# STM32F413CG_WM8731.net
KiCad netlist of a schematic drawn in EAGLE
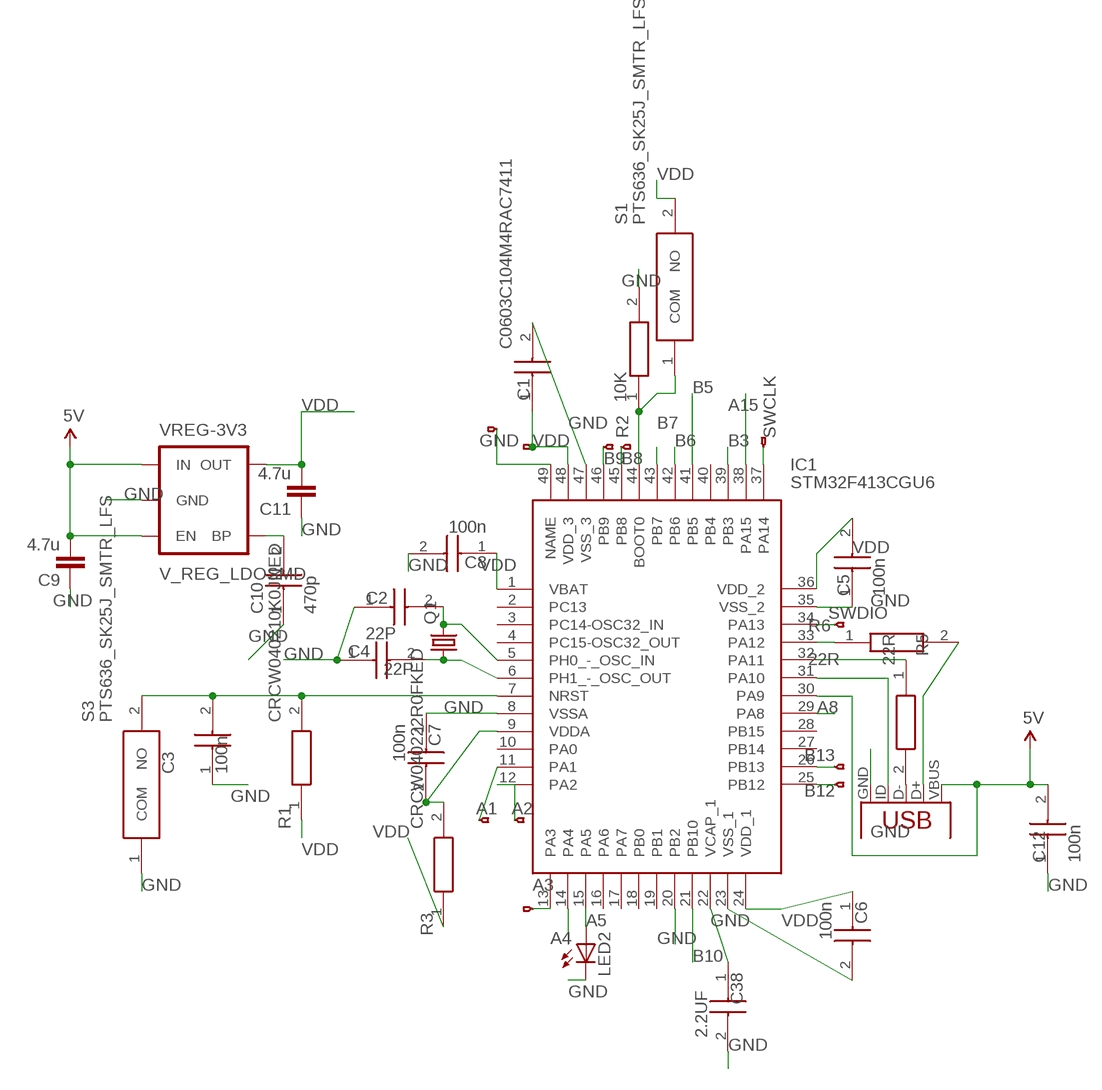
[diagram p0: schematic, sheet 1]
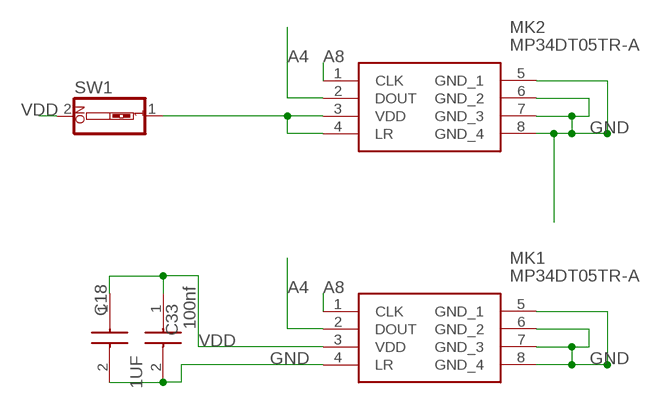
[diagram p1: schematic, sheet 2]
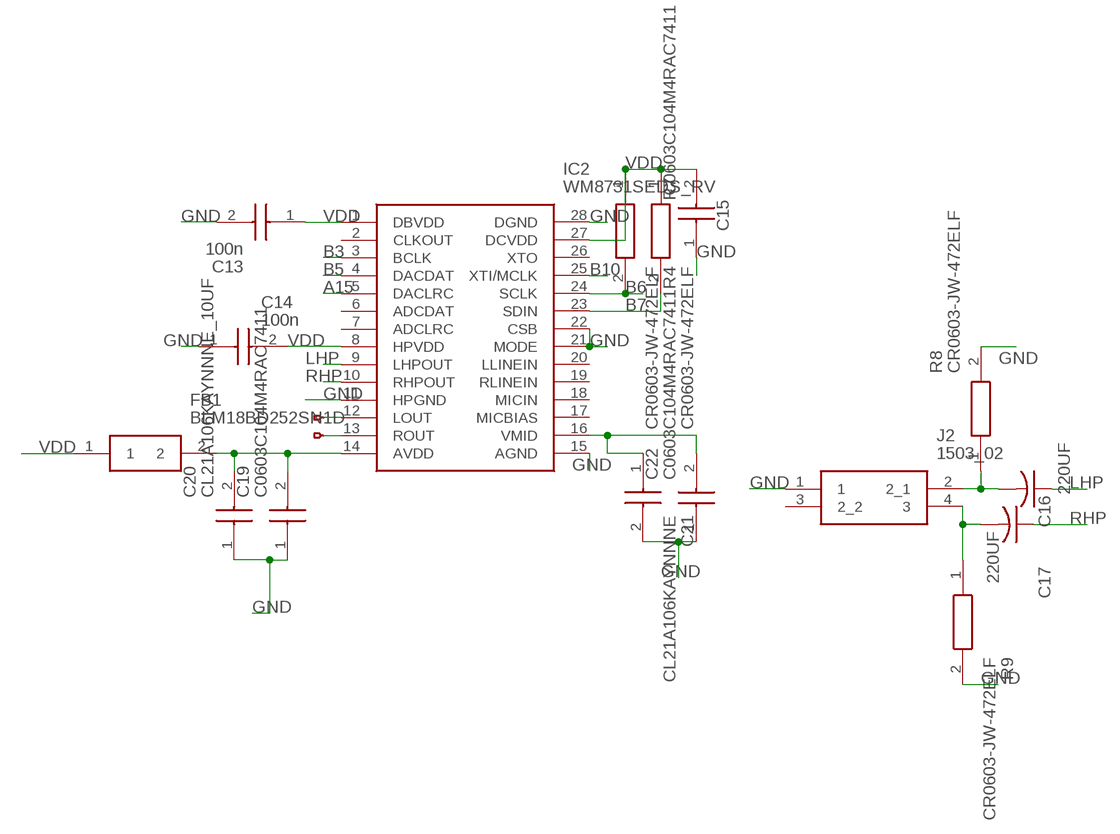
[diagram p2: schematic, sheet 3]

(export (version "E")
  (design (tool "Eeschema 10.0.6"))
  (components
    (comp (ref "C13")
      (value "100n")
      (footprint "eagle-import:CAPC1608X95N")
      (fields
        (field (name "MANUFACTURER_PART_NUMBER") "C0603C104M4RAC7411")
        (field (name "MOUSER_PART_NUMBER") "80-C0603C104M4R7411")
      )
      (libsource (lib "eagle-import") (part "C0603C104M4RAC7411"))
    )
    (comp (ref "C14")
      (value "100n")
      (footprint "eagle-import:CAPC1608X95N")
      (fields
        (field (name "MANUFACTURER_PART_NUMBER") "C0603C104M4RAC7411")
        (field (name "MOUSER_PART_NUMBER") "80-C0603C104M4R7411")
      )
      (libsource (lib "eagle-import") (part "C0603C104M4RAC7411"))
    )
    (comp (ref "C15")
      (value "C0603C104M4RAC7411")
      (footprint "eagle-import:CAPC1608X95N")
      (fields (field (name "MOUSER_PART_NUMBER") "80-C0603C104M4R7411"))
      (libsource (lib "eagle-import") (part "C0603C104M4RAC7411"))
    )
    (comp (ref "C16")
      (value "220UF")
      (footprint "eagle-import:C025-024X044")
      (libsource (lib "eagle-import") (part "C-US025-024X044"))
    )
    (comp (ref "C17")
      (value "220UF")
      (footprint "eagle-import:C025-024X044")
      (libsource (lib "eagle-import") (part "C-US025-024X044"))
    )
    (comp (ref "C19")
      (value "C0603C104M4RAC7411")
      (footprint "eagle-import:CAPC1608X95N")
      (fields (field (name "MOUSER_PART_NUMBER") "80-C0603C104M4R7411"))
      (libsource (lib "eagle-import") (part "C0603C104M4RAC7411_100nF_C0603C104M4RAC7411"))
    )
    (comp (ref "C20")
      (value "CL21A106KAYNNNE_10UF")
      (footprint "eagle-import:CAPC2012X145N")
      (fields (field (name "MANUFACTURER_PART_NUMBER") "CL21A106KAYNNNE"))
      (libsource (lib "eagle-import") (part "CL21A106KAYNNNE"))
    )
    (comp (ref "C21")
      (value "CL21A106KAYNNNE")
      (footprint "eagle-import:CAPC2012X145N")
      (libsource (lib "eagle-import") (part "CL21A106KAYNNNE"))
    )
    (comp (ref "C22")
      (value "C0603C104M4RAC7411")
      (footprint "eagle-import:CAPC1608X95N")
      (fields (field (name "MOUSER_PART_NUMBER") "80-C0603C104M4R7411"))
      (libsource (lib "eagle-import") (part "C0603C104M4RAC7411_100nF_C0603C104M4RAC7411"))
    )
    (comp (ref "FB1")
      (value "BLM18BD252SN1D")
      (footprint "eagle-import:BEADC1608X95N")
      (fields
        (field (name "MOUSER_PART_NUMBER") "81-BLM18BD252SN1D")
        (field (name "RS_PART_NUMBER") "7241321P")
      )
      (libsource (lib "eagle-import") (part "BLM18BD252SN1D"))
    )
    (comp (ref "IC2")
      (value "WM8731SEDS_RV")
      (footprint "eagle-import:SOP65P780X200-28N")
      (fields (field (name "MANUFACTURER_PART_NUMBER") "WM8731SEDS/RV"))
      (libsource (lib "eagle-import") (part "WM8731SEDS_RV"))
    )
    (comp (ref "J2")
      (value "1503_02")
      (footprint "eagle-import:150302")
      (fields (field (name "MANUFACTURER_PART_NUMBER") "1503 02"))
      (libsource (lib "eagle-import") (part "1503_02"))
    )
    (comp (ref "JP12")
      (value "HEADERHOLE-HEADERHOLE")
      (footprint "eagle-import:1X1-HEADER-HOLE")
      (libsource (lib "eagle-import") (part "HEADERHOLE-HEADERHOLE"))
    )
    (comp (ref "JP13")
      (value "HEADERHOLE-HEADERHOLE")
      (footprint "eagle-import:1X1-HEADER-HOLE")
      (libsource (lib "eagle-import") (part "HEADERHOLE-HEADERHOLE"))
    )
    (comp (ref "R4")
      (value "CR0603-JW-472ELF")
      (footprint "eagle-import:RESC1608X55N")
      (fields
        (field (name "MOUSER_PART_NUMBER") "652-CR0603-JW-472ELF")
        (field (name "RS_PART_NUMBER") "7408956P")
      )
      (libsource (lib "eagle-import") (part "CR0603-JW-472ELF"))
    )
    (comp (ref "R7")
      (value "CR0603-JW-472ELF")
      (footprint "eagle-import:RESC1608X55N")
      (fields
        (field (name "MOUSER_PART_NUMBER") "652-CR0603-JW-472ELF")
        (field (name "RS_PART_NUMBER") "7408956P")
      )
      (libsource (lib "eagle-import") (part "CR0603-JW-472ELF"))
    )
    (comp (ref "R8")
      (value "CR0603-JW-472ELF")
      (footprint "eagle-import:RESC1608X55N")
      (fields
        (field (name "MOUSER_PART_NUMBER") "652-CR0603-JW-472ELF")
        (field (name "RS_PART_NUMBER") "7408956P")
      )
      (libsource (lib "eagle-import") (part "CR0603-JW-472ELF"))
    )
    (comp (ref "R9")
      (value "CR0603-JW-472ELF")
      (footprint "eagle-import:RESC1608X55N")
      (fields
        (field (name "MOUSER_PART_NUMBER") "652-CR0603-JW-472ELF")
        (field (name "RS_PART_NUMBER") "7408956P")
      )
      (libsource (lib "eagle-import") (part "CR0603-JW-472ELF"))
    )
    (comp (ref "C18")
      (value "1UF")
      (footprint "eagle-import:CAPC1005X55N")
      (fields
        (field (name "MANUFACTURER_PART_NUMBER") "CC0402KRX5R6BB105")
        (field (name "MOUSER_PART_NUMBER") "603-CC402KRX5R6BB105")
      )
      (libsource (lib "eagle-import") (part "CC0402KRX5R6BB105"))
    )
    (comp (ref "C33")
      (value "100nf")
      (footprint "eagle-import:CAPC1608X95N")
      (fields
        (field (name "MANUFACTURER_PART_NUMBER") "C0603C104M4RAC7411")
        (field (name "MOUSER_PART_NUMBER") "80-C0603C104M4R7411")
      )
      (libsource (lib "eagle-import") (part "C0603C104M4RAC7411"))
    )
    (comp (ref "MK1")
      (value "MP34DT05TR-A")
      (footprint "eagle-import:MP34DT05TRA")
      (fields (field (name "MOUSER_PART_NUMBER") "511-MP34DT05TR-A"))
      (libsource (lib "eagle-import") (part "MP34DT05TR-A"))
    )
    (comp (ref "MK2")
      (value "MP34DT05TR-A")
      (footprint "eagle-import:MP34DT05TRA")
      (fields (field (name "MOUSER_PART_NUMBER") "511-MP34DT05TR-A"))
      (libsource (lib "eagle-import") (part "MP34DT05TR-A"))
    )
    (comp (ref "SW1")
      (value "SW_DIP-1")
      (footprint "eagle-import:EDG-01")
      (libsource (lib "eagle-import") (part "SW_DIP-1"))
    )
    (comp (ref "C1")
      (value "C0603C104M4RAC7411")
      (footprint "eagle-import:CAPC1608X95N")
      (fields (field (name "MOUSER_PART_NUMBER") "80-C0603C104M4R7411"))
      (libsource (lib "eagle-import") (part "C0603C104M4RAC7411"))
    )
    (comp (ref "C2")
      (value "22P")
      (footprint "eagle-import:CAPC1608X80N")
      (fields
        (field (name "MANUFACTURER_PART_NUMBER") "C1608C0G1H150J080AA")
        (field (name "MOUSER_PART_NUMBER") "810-C1608C0G1H150J")
        (field (name "RS_PART_NUMBER") "7882935")
      )
      (libsource (lib "eagle-import") (part "C1608C0G1H150J080AA"))
    )
    (comp (ref "C3")
      (value "100n")
      (footprint "eagle-import:CAPC1608X95N")
      (fields
        (field (name "MANUFACTURER_PART_NUMBER") "C0603C104M4RAC7411")
        (field (name "MOUSER_PART_NUMBER") "80-C0603C104M4R7411")
      )
      (libsource (lib "eagle-import") (part "C0603C104M4RAC7411"))
    )
    (comp (ref "C4")
      (value "22P")
      (footprint "eagle-import:CAPC1608X80N")
      (fields
        (field (name "MANUFACTURER_PART_NUMBER") "C1608C0G1H150J080AA")
        (field (name "MOUSER_PART_NUMBER") "810-C1608C0G1H150J")
        (field (name "RS_PART_NUMBER") "7882935")
      )
      (libsource (lib "eagle-import") (part "C1608C0G1H150J080AA"))
    )
    (comp (ref "C5")
      (value "100n")
      (footprint "eagle-import:CAPC1608X95N")
      (fields
        (field (name "MANUFACTURER_PART_NUMBER") "C0603C104M4RAC7411")
        (field (name "MOUSER_PART_NUMBER") "80-C0603C104M4R7411")
      )
      (libsource (lib "eagle-import") (part "C0603C104M4RAC7411"))
    )
    (comp (ref "C6")
      (value "100n")
      (footprint "eagle-import:CAPC1608X95N")
      (fields
        (field (name "MANUFACTURER_PART_NUMBER") "C0603C104M4RAC7411")
        (field (name "MOUSER_PART_NUMBER") "80-C0603C104M4R7411")
      )
      (libsource (lib "eagle-import") (part "C0603C104M4RAC7411"))
    )
    (comp (ref "C7")
      (value "100n")
      (footprint "eagle-import:CAPC1608X95N")
      (fields
        (field (name "MANUFACTURER_PART_NUMBER") "C0603C104M4RAC7411")
        (field (name "MOUSER_PART_NUMBER") "80-C0603C104M4R7411")
      )
      (libsource (lib "eagle-import") (part "C0603C104M4RAC7411"))
    )
    (comp (ref "C8")
      (value "100n")
      (footprint "eagle-import:CAPC1608X95N")
      (fields
        (field (name "MANUFACTURER_PART_NUMBER") "C0603C104M4RAC7411")
        (field (name "MOUSER_PART_NUMBER") "80-C0603C104M4R7411")
      )
      (libsource (lib "eagle-import") (part "C0603C104M4RAC7411"))
    )
    (comp (ref "C9")
      (value "4.7u")
      (footprint "eagle-import:C2.5-3")
      (libsource (lib "eagle-import") (part "C2,5-3"))
    )
    (comp (ref "C10")
      (value "470p")
      (footprint "eagle-import:CAPC1608X87N")
      (fields
        (field (name "MANUFACTURER_PART_NUMBER") "C0603C471K3RACTU")
        (field (name "MOUSER_PART_NUMBER") "80-C0603C471K3R")
      )
      (libsource (lib "eagle-import") (part "C0603C471K3RACTU"))
    )
    (comp (ref "C11")
      (value "4.7u")
      (footprint "eagle-import:C2.5-3")
      (libsource (lib "eagle-import") (part "C2,5-3"))
    )
    (comp (ref "C12")
      (value "100n")
      (footprint "eagle-import:CAPC1608X95N")
      (fields
        (field (name "MANUFACTURER_PART_NUMBER") "C0603C104M4RAC7411")
        (field (name "MOUSER_PART_NUMBER") "80-C0603C104M4R7411")
      )
      (libsource (lib "eagle-import") (part "C0603C104M4RAC7411"))
    )
    (comp (ref "C38")
      (value "2.2UF")
      (footprint "eagle-import:CAPC2012X145N")
      (fields
        (field (name "MANUFACTURER_PART_NUMBER") "C2012X7R1E225K125AB")
        (field (name "MOUSER_PART_NUMBER") "810-C2012X7R1E225K")
        (field (name "RS_PART_NUMBER") "9159394P")
      )
      (libsource (lib "eagle-import") (part "C2012X7R1E225K125AB"))
    )
    (comp (ref "IC1")
      (value "STM32F413CGU6")
      (footprint "eagle-import:QFN50P700X700X60-49N")
      (fields (field (name "MOUSER_PART_NUMBER") "511-STM32F413CGU6"))
      (libsource (lib "eagle-import") (part "STM32F413CGU6"))
    )
    (comp (ref "JP1")
      (value "HEADERHOLE-HEADERHOLE")
      (footprint "eagle-import:1X1-HEADER-HOLE")
      (libsource (lib "eagle-import") (part "HEADERHOLE-HEADERHOLE"))
    )
    (comp (ref "JP2")
      (value "HEADERHOLE-HEADERHOLE")
      (footprint "eagle-import:1X1-HEADER-HOLE")
      (libsource (lib "eagle-import") (part "HEADERHOLE-HEADERHOLE"))
    )
    (comp (ref "JP3")
      (value "HEADERHOLE-HEADERHOLE")
      (footprint "eagle-import:1X1-HEADER-HOLE")
      (libsource (lib "eagle-import") (part "HEADERHOLE-HEADERHOLE"))
    )
    (comp (ref "JP4")
      (value "HEADERHOLE-HEADERHOLE")
      (footprint "eagle-import:1X1-HEADER-HOLE")
      (libsource (lib "eagle-import") (part "HEADERHOLE-HEADERHOLE"))
    )
    (comp (ref "JP5")
      (value "HEADERHOLE-HEADERHOLE")
      (footprint "eagle-import:1X1-HEADER-HOLE")
      (libsource (lib "eagle-import") (part "HEADERHOLE-HEADERHOLE"))
    )
    (comp (ref "JP6")
      (value "HEADERHOLE-HEADERHOLE")
      (footprint "eagle-import:1X1-HEADER-HOLE")
      (libsource (lib "eagle-import") (part "HEADERHOLE-HEADERHOLE"))
    )
    (comp (ref "JP7")
      (value "HEADERHOLE-HEADERHOLE")
      (footprint "eagle-import:1X1-HEADER-HOLE")
      (libsource (lib "eagle-import") (part "HEADERHOLE-HEADERHOLE"))
    )
    (comp (ref "JP8")
      (value "HEADERHOLE-HEADERHOLE")
      (footprint "eagle-import:1X1-HEADER-HOLE")
      (libsource (lib "eagle-import") (part "HEADERHOLE-HEADERHOLE"))
    )
    (comp (ref "JP9")
      (value "HEADERHOLE-HEADERHOLE")
      (footprint "eagle-import:1X1-HEADER-HOLE")
      (libsource (lib "eagle-import") (part "HEADERHOLE-HEADERHOLE"))
    )
    (comp (ref "JP10")
      (value "HEADERHOLE-HEADERHOLE")
      (footprint "eagle-import:1X1-HEADER-HOLE")
      (libsource (lib "eagle-import") (part "HEADERHOLE-HEADERHOLE"))
    )
    (comp (ref "JP11")
      (value "HEADERHOLE-HEADERHOLE")
      (footprint "eagle-import:1X1-HEADER-HOLE")
      (libsource (lib "eagle-import") (part "HEADERHOLE-HEADERHOLE"))
    )
    (comp (ref "LED2")
      (value "LED0603")
      (footprint "eagle-import:LED-0603")
      (libsource (lib "eagle-import") (part "LED0603"))
    )
    (comp (ref "Q1")
      (value "CRYSTALHC49S")
      (footprint "eagle-import:HC49_S")
      (libsource (lib "eagle-import") (part "CRYSTALHC49S"))
    )
    (comp (ref "R1")
      (value "CRCW040210K0JNED")
      (footprint "eagle-import:RESC1005X40N")
      (fields (field (name "MOUSER_PART_NUMBER") "71-CRCW0402J-10K-E3"))
      (libsource (lib "eagle-import") (part "CRCW040210K0JNED"))
    )
    (comp (ref "R2")
      (value "10K")
      (footprint "eagle-import:RESC1005X40N")
      (fields
        (field (name "MANUFACTURER_PART_NUMBER") "CRCW040210K0JNED")
        (field (name "MOUSER_PART_NUMBER") "71-CRCW0402J-10K-E3")
      )
      (libsource (lib "eagle-import") (part "CRCW040210K0JNED"))
    )
    (comp (ref "R3")
      (value "CRCW040222R0FKED")
      (footprint "eagle-import:RESC1005X40N")
      (fields
        (field (name "MOUSER_PART_NUMBER") "71-CRCW0402-22-E3")
        (field (name "RS_PART_NUMBER") "6788983P")
      )
      (libsource (lib "eagle-import") (part "CRCW040222R0FKED"))
    )
    (comp (ref "R5")
      (value "22R")
      (footprint "eagle-import:RESC1005X40N")
      (fields
        (field (name "MANUFACTURER_PART_NUMBER") "CRCW040222R0FKED")
        (field (name "MOUSER_PART_NUMBER") "71-CRCW0402-22-E3")
        (field (name "RS_PART_NUMBER") "6788983P")
      )
      (libsource (lib "eagle-import") (part "CRCW040222R0FKED"))
    )
    (comp (ref "R6")
      (value "22R")
      (footprint "eagle-import:RESC1005X40N")
      (fields
        (field (name "MANUFACTURER_PART_NUMBER") "CRCW040222R0FKED")
        (field (name "MOUSER_PART_NUMBER") "71-CRCW0402-22-E3")
        (field (name "RS_PART_NUMBER") "6788983P")
      )
      (libsource (lib "eagle-import") (part "CRCW040222R0FKED"))
    )
    (comp (ref "S1")
      (value "PTS636_SK25J_SMTR_LFS")
      (footprint "eagle-import:PTS636SK25JSMTRLFS")
      (fields
        (field (name "MANUFACTURER_PART_NUMBER") "PTS636 SK25J SMTR LFS")
        (field (name "MOUSER_PART_NUMBER") "611-PTS636SK25JSMTRL")
      )
      (libsource (lib "eagle-import") (part "PTS636_SK25J_SMTR_LFS"))
    )
    (comp (ref "S3")
      (value "PTS636_SK25J_SMTR_LFS")
      (footprint "eagle-import:PTS636SK25JSMTRLFS")
      (fields
        (field (name "MANUFACTURER_PART_NUMBER") "PTS636 SK25J SMTR LFS")
        (field (name "MOUSER_PART_NUMBER") "611-PTS636SK25JSMTRL")
      )
      (libsource (lib "eagle-import") (part "PTS636_SK25J_SMTR_LFS"))
    )
    (comp (ref "VREG-3V3")
      (value "V_REG_LDOSMD")
      (footprint "eagle-import:SOT23-5")
      (libsource (lib "eagle-import") (part "V_REG_LDOSMD"))
    )
    (comp (ref "X1")
      (value "USB-MICROB-SMD")
      (footprint "eagle-import:USB-MICROB-SMD")
      (libsource (lib "eagle-import") (part "USB-MICROB-SMD"))
    )
  )
  (nets
    (net (code "1") (name "5V") (class "Default")
      (node (ref "C12") (pin "2") (pinfunction "2_2") (pintype "bidirectional"))
      (node (ref "C9") (pin "2") (pinfunction "2_2") (pintype "passive"))
      (node (ref "IC1") (pin "30") (pinfunction "PA9_30") (pintype "bidirectional"))
      (node (ref "VREG-3V3") (pin "1") (pinfunction "IN_1") (pintype "input"))
      (node (ref "VREG-3V3") (pin "3") (pinfunction "EN_3") (pintype "input"))
      (node (ref "X1") (pin "VBUS") (pinfunction "VBUS_VBUS") (pintype "bidirectional"))
    )
    (net (code "2") (name "A1") (class "Default")
      (node (ref "IC1") (pin "11") (pinfunction "PA1_11") (pintype "bidirectional"))
      (node (ref "JP8") (pin "1") (pinfunction "P$1_1") (pintype "bidirectional"))
    )
    (net (code "3") (name "A2") (class "Default")
      (node (ref "IC1") (pin "12") (pinfunction "PA2_12") (pintype "bidirectional"))
      (node (ref "JP9") (pin "1") (pinfunction "P$1_1") (pintype "bidirectional"))
    )
    (net (code "4") (name "A3") (class "Default")
      (node (ref "IC1") (pin "13") (pinfunction "PA3_13") (pintype "bidirectional"))
      (node (ref "JP10") (pin "1") (pinfunction "P$1_1") (pintype "bidirectional"))
    )
    (net (code "5") (name "A4") (class "Default")
      (node (ref "IC1") (pin "14") (pinfunction "PA4_14") (pintype "bidirectional"))
      (node (ref "MK1") (pin "2") (pinfunction "DOUT_2") (pintype "bidirectional"))
      (node (ref "MK2") (pin "2") (pinfunction "DOUT_2") (pintype "bidirectional"))
    )
    (net (code "6") (name "A5") (class "Default")
      (node (ref "IC1") (pin "15") (pinfunction "PA5_15") (pintype "bidirectional"))
      (node (ref "LED2") (pin "A") (pinfunction "A_A") (pintype "passive"))
    )
    (net (code "7") (name "A8") (class "Default")
      (node (ref "IC1") (pin "29") (pinfunction "PA8_29") (pintype "bidirectional"))
      (node (ref "MK1") (pin "1") (pinfunction "CLK_1") (pintype "bidirectional"))
      (node (ref "MK2") (pin "1") (pinfunction "CLK_1") (pintype "bidirectional"))
    )
    (net (code "8") (name "A15") (class "Default")
      (node (ref "IC1") (pin "38") (pinfunction "PA15_38") (pintype "bidirectional"))
      (node (ref "IC2") (pin "5") (pinfunction "DACLRC_5") (pintype "bidirectional"))
    )
    (net (code "9") (name "B3") (class "Default")
      (node (ref "IC1") (pin "39") (pinfunction "PB3_39") (pintype "bidirectional"))
      (node (ref "IC2") (pin "3") (pinfunction "BCLK_3") (pintype "bidirectional"))
    )
    (net (code "10") (name "B5") (class "Default")
      (node (ref "IC1") (pin "41") (pinfunction "PB5_41") (pintype "bidirectional"))
      (node (ref "IC2") (pin "4") (pinfunction "DACDAT_4") (pintype "bidirectional"))
    )
    (net (code "11") (name "B6") (class "Default")
      (node (ref "IC1") (pin "42") (pinfunction "PB6_42") (pintype "bidirectional"))
      (node (ref "IC2") (pin "24") (pinfunction "SCLK_24") (pintype "bidirectional"))
      (node (ref "R4") (pin "2") (pinfunction "2_2") (pintype "bidirectional"))
    )
    (net (code "12") (name "B7") (class "Default")
      (node (ref "IC1") (pin "43") (pinfunction "PB7_43") (pintype "bidirectional"))
      (node (ref "IC2") (pin "23") (pinfunction "SDIN_23") (pintype "bidirectional"))
      (node (ref "R7") (pin "2") (pinfunction "2_2") (pintype "bidirectional"))
    )
    (net (code "13") (name "B8") (class "Default")
      (node (ref "IC1") (pin "45") (pinfunction "PB8_45") (pintype "bidirectional"))
      (node (ref "JP5") (pin "1") (pinfunction "P$1_1") (pintype "bidirectional"))
    )
    (net (code "14") (name "B9") (class "Default")
      (node (ref "IC1") (pin "46") (pinfunction "PB9_46") (pintype "bidirectional"))
      (node (ref "JP11") (pin "1") (pinfunction "P$1_1") (pintype "bidirectional"))
    )
    (net (code "15") (name "B10") (class "Default")
      (node (ref "IC1") (pin "21") (pinfunction "PB10_21") (pintype "bidirectional"))
      (node (ref "IC2") (pin "25") (pinfunction "XTI/MCLK_25") (pintype "bidirectional"))
    )
    (net (code "16") (name "B12") (class "Default")
      (node (ref "IC1") (pin "25") (pinfunction "PB12_25") (pintype "bidirectional"))
      (node (ref "JP7") (pin "1") (pinfunction "P$1_1") (pintype "bidirectional"))
    )
    (net (code "17") (name "B13") (class "Default")
      (node (ref "IC1") (pin "26") (pinfunction "PB13_26") (pintype "bidirectional"))
      (node (ref "JP6") (pin "1") (pinfunction "P$1_1") (pintype "bidirectional"))
    )
    (net (code "18") (name "GND") (class "Default")
      (node (ref "C1") (pin "2") (pinfunction "2_2") (pintype "bidirectional"))
      (node (ref "C10") (pin "1") (pinfunction "1_1") (pintype "bidirectional"))
      (node (ref "C11") (pin "1") (pinfunction "1_1") (pintype "passive"))
      (node (ref "C12") (pin "1") (pinfunction "1_1") (pintype "bidirectional"))
      (node (ref "C13") (pin "2") (pinfunction "2_2") (pintype "bidirectional"))
      (node (ref "C14") (pin "1") (pinfunction "1_1") (pintype "bidirectional"))
      (node (ref "C15") (pin "1") (pinfunction "1_1") (pintype "bidirectional"))
      (node (ref "C18") (pin "2") (pinfunction "C2_2") (pintype "bidirectional"))
      (node (ref "C19") (pin "1") (pinfunction "1_1") (pintype "bidirectional"))
      (node (ref "C2") (pin "1") (pinfunction "1_1") (pintype "bidirectional"))
      (node (ref "C20") (pin "1") (pinfunction "1_1") (pintype "bidirectional"))
      (node (ref "C21") (pin "2") (pinfunction "2_2") (pintype "bidirectional"))
      (node (ref "C22") (pin "1") (pinfunction "1_1") (pintype "bidirectional"))
      (node (ref "C3") (pin "1") (pinfunction "1_1") (pintype "bidirectional"))
      (node (ref "C33") (pin "2") (pinfunction "2_2") (pintype "bidirectional"))
      (node (ref "C38") (pin "2") (pinfunction "2_2") (pintype "bidirectional"))
      (node (ref "C4") (pin "1") (pinfunction "1_1") (pintype "bidirectional"))
      (node (ref "C5") (pin "1") (pinfunction "1_1") (pintype "bidirectional"))
      (node (ref "C6") (pin "2") (pinfunction "2_2") (pintype "bidirectional"))
      (node (ref "C7") (pin "1") (pinfunction "1_1") (pintype "bidirectional"))
      (node (ref "C8") (pin "2") (pinfunction "2_2") (pintype "bidirectional"))
      (node (ref "C9") (pin "1") (pinfunction "1_1") (pintype "passive"))
      (node (ref "IC1") (pin "20") (pinfunction "PB2_20") (pintype "bidirectional"))
      (node (ref "IC1") (pin "23") (pinfunction "VSS_1_23") (pintype "power_in"))
      (node (ref "IC1") (pin "35") (pinfunction "VSS_2_35") (pintype "power_in"))
      (node (ref "IC1") (pin "47") (pinfunction "VSS_3_47") (pintype "power_in"))
      (node (ref "IC1") (pin "49") (pinfunction "NAME_49") (pintype "bidirectional"))
      (node (ref "IC1") (pin "8") (pinfunction "VSSA_8") (pintype "power_in"))
      (node (ref "IC2") (pin "11") (pinfunction "HPGND_11") (pintype "bidirectional"))
      (node (ref "IC2") (pin "15") (pinfunction "AGND_15") (pintype "bidirectional"))
      (node (ref "IC2") (pin "21") (pinfunction "MODE_21") (pintype "bidirectional"))
      (node (ref "IC2") (pin "22") (pinfunction "CSB_22") (pintype "bidirectional"))
      (node (ref "IC2") (pin "28") (pinfunction "DGND_28") (pintype "bidirectional"))
      (node (ref "J2") (pin "1") (pinfunction "1_1") (pintype "bidirectional"))
      (node (ref "JP1") (pin "1") (pinfunction "P$1_1") (pintype "bidirectional"))
      (node (ref "LED2") (pin "C") (pinfunction "C_C") (pintype "passive"))
      (node (ref "MK1") (pin "4") (pinfunction "LR_4") (pintype "bidirectional"))
      (node (ref "MK1") (pin "5") (pinfunction "GND_1_5") (pintype "bidirectional"))
      (node (ref "MK1") (pin "6") (pinfunction "GND_2_6") (pintype "bidirectional"))
      (node (ref "MK1") (pin "7") (pinfunction "GND_3_7") (pintype "bidirectional"))
      (node (ref "MK1") (pin "8") (pinfunction "GND_4_8") (pintype "bidirectional"))
      (node (ref "MK2") (pin "5") (pinfunction "GND_1_5") (pintype "bidirectional"))
      (node (ref "MK2") (pin "6") (pinfunction "GND_2_6") (pintype "bidirectional"))
      (node (ref "MK2") (pin "7") (pinfunction "GND_3_7") (pintype "bidirectional"))
      (node (ref "MK2") (pin "8") (pinfunction "GND_4_8") (pintype "bidirectional"))
      (node (ref "R2") (pin "2") (pinfunction "2_2") (pintype "bidirectional"))
      (node (ref "R8") (pin "2") (pinfunction "2_2") (pintype "bidirectional"))
      (node (ref "R9") (pin "2") (pinfunction "2_2") (pintype "bidirectional"))
      (node (ref "S3") (pin "1") (pinfunction "COM_1") (pintype "bidirectional"))
      (node (ref "VREG-3V3") (pin "2") (pinfunction "GND_2") (pintype "input"))
      (node (ref "X1") (pin "GND") (pinfunction "GND_GND") (pintype "bidirectional"))
    )
    (net (code "19") (name "LHP") (class "Default")
      (node (ref "C16") (pin "1") (pinfunction "1_1") (pintype "passive"))
      (node (ref "IC2") (pin "9") (pinfunction "LHPOUT_9") (pintype "bidirectional"))
    )
    (net (code "20") (name "Net-(IC1-BOOT0)") (class "Default")
      (node (ref "IC1") (pin "44") (pinfunction "BOOT0_44") (pintype "bidirectional"))
      (node (ref "R2") (pin "1") (pinfunction "1_1") (pintype "bidirectional"))
      (node (ref "S1") (pin "1") (pinfunction "COM_1") (pintype "bidirectional"))
    )
    (net (code "21") (name "Net-(IC1-NRST)") (class "Default")
      (node (ref "C3") (pin "2") (pinfunction "2_2") (pintype "bidirectional"))
      (node (ref "IC1") (pin "7") (pinfunction "NRST_7") (pintype "bidirectional"))
      (node (ref "R1") (pin "2") (pinfunction "2_2") (pintype "bidirectional"))
      (node (ref "S3") (pin "2") (pinfunction "NO_2") (pintype "bidirectional"))
    )
    (net (code "22") (name "Net-(IC1-PA10)") (class "Default")
      (node (ref "IC1") (pin "31") (pinfunction "PA10_31") (pintype "bidirectional"))
      (node (ref "X1") (pin "ID") (pinfunction "ID_ID") (pintype "bidirectional"))
    )
    (net (code "23") (name "Net-(IC1-PA11)") (class "Default")
      (node (ref "IC1") (pin "32") (pinfunction "PA11_32") (pintype "bidirectional"))
      (node (ref "R5") (pin "1") (pinfunction "1_1") (pintype "bidirectional"))
    )
    (net (code "24") (name "Net-(IC1-PA12)") (class "Default")
      (node (ref "IC1") (pin "33") (pinfunction "PA12_33") (pintype "bidirectional"))
      (node (ref "R6") (pin "1") (pinfunction "1_1") (pintype "bidirectional"))
    )
    (net (code "25") (name "Net-(IC1-PH0_-_OSC_IN)") (class "Default")
      (node (ref "C2") (pin "2") (pinfunction "2_2") (pintype "bidirectional"))
      (node (ref "IC1") (pin "5") (pinfunction "PH0_-_OSC_IN_5") (pintype "bidirectional"))
      (node (ref "Q1") (pin "2") (pinfunction "2_2") (pintype "passive"))
    )
    (net (code "26") (name "Net-(IC1-PH1_-_OSC_OUT)") (class "Default")
      (node (ref "C4") (pin "2") (pinfunction "2_2") (pintype "bidirectional"))
      (node (ref "IC1") (pin "6") (pinfunction "PH1_-_OSC_OUT_6") (pintype "bidirectional"))
      (node (ref "Q1") (pin "1") (pinfunction "1_1") (pintype "passive"))
    )
    (net (code "27") (name "Net-(IC1-VCAP_1)") (class "Default")
      (node (ref "C38") (pin "1") (pinfunction "1_1") (pintype "bidirectional"))
      (node (ref "IC1") (pin "22") (pinfunction "VCAP_1_22") (pintype "power_in"))
    )
    (net (code "28") (name "Net-(IC1-VDDA)") (class "Default")
      (node (ref "C7") (pin "2") (pinfunction "2_2") (pintype "bidirectional"))
      (node (ref "IC1") (pin "9") (pinfunction "VDDA_9") (pintype "power_in"))
      (node (ref "R3") (pin "2") (pinfunction "2_2") (pintype "bidirectional"))
    )
    (net (code "29") (name "Net-(IC2-AVDD)") (class "Default")
      (node (ref "C19") (pin "2") (pinfunction "2_2") (pintype "bidirectional"))
      (node (ref "C20") (pin "2") (pinfunction "2_2") (pintype "bidirectional"))
      (node (ref "FB1") (pin "2") (pinfunction "2_2") (pintype "bidirectional"))
      (node (ref "IC2") (pin "14") (pinfunction "AVDD_14") (pintype "bidirectional"))
    )
    (net (code "30") (name "Net-(IC2-LOUT)") (class "Default")
      (node (ref "IC2") (pin "12") (pinfunction "LOUT_12") (pintype "bidirectional"))
      (node (ref "JP13") (pin "1") (pinfunction "P$1_1") (pintype "bidirectional"))
    )
    (net (code "31") (name "Net-(IC2-ROUT)") (class "Default")
      (node (ref "IC2") (pin "13") (pinfunction "ROUT_13") (pintype "bidirectional"))
      (node (ref "JP12") (pin "1") (pinfunction "P$1_1") (pintype "bidirectional"))
    )
    (net (code "32") (name "Net-(IC2-VMID)") (class "Default")
      (node (ref "C21") (pin "1") (pinfunction "1_1") (pintype "bidirectional"))
      (node (ref "C22") (pin "2") (pinfunction "2_2") (pintype "bidirectional"))
      (node (ref "IC2") (pin "16") (pinfunction "VMID_16") (pintype "bidirectional"))
    )
    (net (code "33") (name "Net-(J2-2_1)") (class "Default")
      (node (ref "C16") (pin "2") (pinfunction "2_2") (pintype "passive"))
      (node (ref "J2") (pin "2") (pinfunction "2_1_2") (pintype "bidirectional"))
      (node (ref "R8") (pin "1") (pinfunction "1_1") (pintype "bidirectional"))
    )
    (net (code "34") (name "Net-(J2-3)") (class "Default")
      (node (ref "C17") (pin "2") (pinfunction "2_2") (pintype "passive"))
      (node (ref "J2") (pin "4") (pinfunction "3_4") (pintype "bidirectional"))
      (node (ref "R9") (pin "1") (pinfunction "1_1") (pintype "bidirectional"))
    )
    (net (code "35") (name "Net-(MK2-LR)") (class "Default")
      (node (ref "MK2") (pin "3") (pinfunction "VDD_3") (pintype "bidirectional"))
      (node (ref "MK2") (pin "4") (pinfunction "LR_4") (pintype "bidirectional"))
      (node (ref "SW1") (pin "1") (pinfunction "1_1") (pintype "passive"))
    )
    (net (code "36") (name "Net-(R5-Pad2)") (class "Default")
      (node (ref "R5") (pin "2") (pinfunction "2_2") (pintype "bidirectional"))
      (node (ref "X1") (pin "D-") (pinfunction "D-_D-") (pintype "bidirectional"))
    )
    (net (code "37") (name "Net-(R6-Pad2)") (class "Default")
      (node (ref "R6") (pin "2") (pinfunction "2_2") (pintype "bidirectional"))
      (node (ref "X1") (pin "D+") (pinfunction "D+_D+") (pintype "bidirectional"))
    )
    (net (code "38") (name "Net-(VREG-3V3-BP)") (class "Default")
      (node (ref "C10") (pin "2") (pinfunction "2_2") (pintype "bidirectional"))
      (node (ref "VREG-3V3") (pin "4") (pinfunction "BP_4") (pintype "input"))
    )
    (net (code "39") (name "RHP") (class "Default")
      (node (ref "C17") (pin "1") (pinfunction "1_1") (pintype "passive"))
      (node (ref "IC2") (pin "10") (pinfunction "RHPOUT_10") (pintype "bidirectional"))
    )
    (net (code "40") (name "SWCLK") (class "Default")
      (node (ref "IC1") (pin "37") (pinfunction "PA14_37") (pintype "bidirectional"))
      (node (ref "JP2") (pin "1") (pinfunction "P$1_1") (pintype "bidirectional"))
    )
    (net (code "41") (name "SWDIO") (class "Default")
      (node (ref "IC1") (pin "34") (pinfunction "PA13_34") (pintype "bidirectional"))
      (node (ref "JP3") (pin "1") (pinfunction "P$1_1") (pintype "bidirectional"))
    )
    (net (code "42") (name "VDD") (class "Default")
      (node (ref "C1") (pin "1") (pinfunction "1_1") (pintype "bidirectional"))
      (node (ref "C11") (pin "2") (pinfunction "2_2") (pintype "passive"))
      (node (ref "C13") (pin "1") (pinfunction "1_1") (pintype "bidirectional"))
      (node (ref "C14") (pin "2") (pinfunction "2_2") (pintype "bidirectional"))
      (node (ref "C15") (pin "2") (pinfunction "2_2") (pintype "bidirectional"))
      (node (ref "C18") (pin "1") (pinfunction "C1_1") (pintype "bidirectional"))
      (node (ref "C33") (pin "1") (pinfunction "1_1") (pintype "bidirectional"))
      (node (ref "C5") (pin "2") (pinfunction "2_2") (pintype "bidirectional"))
      (node (ref "C6") (pin "1") (pinfunction "1_1") (pintype "bidirectional"))
      (node (ref "C8") (pin "1") (pinfunction "1_1") (pintype "bidirectional"))
      (node (ref "FB1") (pin "1") (pinfunction "1_1") (pintype "bidirectional"))
      (node (ref "IC1") (pin "1") (pinfunction "VBAT_1") (pintype "power_in"))
      (node (ref "IC1") (pin "24") (pinfunction "VDD_1_24") (pintype "power_in"))
      (node (ref "IC1") (pin "36") (pinfunction "VDD_2_36") (pintype "power_in"))
      (node (ref "IC1") (pin "48") (pinfunction "VDD_3_48") (pintype "power_in"))
      (node (ref "IC2") (pin "1") (pinfunction "DBVDD_1") (pintype "bidirectional"))
      (node (ref "IC2") (pin "27") (pinfunction "DCVDD_27") (pintype "bidirectional"))
      (node (ref "IC2") (pin "8") (pinfunction "HPVDD_8") (pintype "bidirectional"))
      (node (ref "JP4") (pin "1") (pinfunction "P$1_1") (pintype "bidirectional"))
      (node (ref "MK1") (pin "3") (pinfunction "VDD_3") (pintype "bidirectional"))
      (node (ref "R1") (pin "1") (pinfunction "1_1") (pintype "bidirectional"))
      (node (ref "R3") (pin "1") (pinfunction "1_1") (pintype "bidirectional"))
      (node (ref "R4") (pin "1") (pinfunction "1_1") (pintype "bidirectional"))
      (node (ref "R7") (pin "1") (pinfunction "1_1") (pintype "bidirectional"))
      (node (ref "S1") (pin "2") (pinfunction "NO_2") (pintype "bidirectional"))
      (node (ref "SW1") (pin "2") (pinfunction "2_2") (pintype "passive"))
      (node (ref "VREG-3V3") (pin "5") (pinfunction "OUT_5") (pintype "passive"))
    )
    (net (code "43") (name "unconnected-(IC1-PA0-Pad10)") (class "Default")
      (node (ref "IC1") (pin "10") (pinfunction "PA0_10") (pintype "bidirectional"))
    )
    (net (code "44") (name "unconnected-(IC1-PA6-Pad16)") (class "Default")
      (node (ref "IC1") (pin "16") (pinfunction "PA6_16") (pintype "bidirectional"))
    )
    (net (code "45") (name "unconnected-(IC1-PA7-Pad17)") (class "Default")
      (node (ref "IC1") (pin "17") (pinfunction "PA7_17") (pintype "bidirectional"))
    )
    (net (code "46") (name "unconnected-(IC1-PB0-Pad18)") (class "Default")
      (node (ref "IC1") (pin "18") (pinfunction "PB0_18") (pintype "bidirectional"))
    )
    (net (code "47") (name "unconnected-(IC1-PB1-Pad19)") (class "Default")
      (node (ref "IC1") (pin "19") (pinfunction "PB1_19") (pintype "bidirectional"))
    )
    (net (code "48") (name "unconnected-(IC1-PB4-Pad40)") (class "Default")
      (node (ref "IC1") (pin "40") (pinfunction "PB4_40") (pintype "bidirectional"))
    )
    (net (code "49") (name "unconnected-(IC1-PB14-Pad27)") (class "Default")
      (node (ref "IC1") (pin "27") (pinfunction "PB14_27") (pintype "bidirectional"))
    )
    (net (code "50") (name "unconnected-(IC1-PB15-Pad28)") (class "Default")
      (node (ref "IC1") (pin "28") (pinfunction "PB15_28") (pintype "bidirectional"))
    )
    (net (code "51") (name "unconnected-(IC1-PC13-Pad2)") (class "Default")
      (node (ref "IC1") (pin "2") (pinfunction "PC13_2") (pintype "bidirectional"))
    )
    (net (code "52") (name "unconnected-(IC1-PC14-OSC32_IN-Pad3)") (class "Default")
      (node (ref "IC1") (pin "3") (pinfunction "PC14-OSC32_IN_3") (pintype "bidirectional"))
    )
    (net (code "53") (name "unconnected-(IC1-PC15-OSC32_OUT-Pad4)") (class "Default")
      (node (ref "IC1") (pin "4") (pinfunction "PC15-OSC32_OUT_4") (pintype "bidirectional"))
    )
    (net (code "54") (name "unconnected-(IC2-ADCDAT-Pad6)") (class "Default")
      (node (ref "IC2") (pin "6") (pinfunction "ADCDAT_6") (pintype "bidirectional"))
    )
    (net (code "55") (name "unconnected-(IC2-ADCLRC-Pad7)") (class "Default")
      (node (ref "IC2") (pin "7") (pinfunction "ADCLRC_7") (pintype "bidirectional"))
    )
    (net (code "56") (name "unconnected-(IC2-CLKOUT-Pad2)") (class "Default")
      (node (ref "IC2") (pin "2") (pinfunction "CLKOUT_2") (pintype "bidirectional"))
    )
    (net (code "57") (name "unconnected-(IC2-LLINEIN-Pad20)") (class "Default")
      (node (ref "IC2") (pin "20") (pinfunction "LLINEIN_20") (pintype "bidirectional"))
    )
    (net (code "58") (name "unconnected-(IC2-MICBIAS-Pad17)") (class "Default")
      (node (ref "IC2") (pin "17") (pinfunction "MICBIAS_17") (pintype "bidirectional"))
    )
    (net (code "59") (name "unconnected-(IC2-MICIN-Pad18)") (class "Default")
      (node (ref "IC2") (pin "18") (pinfunction "MICIN_18") (pintype "bidirectional"))
    )
    (net (code "60") (name "unconnected-(IC2-RLINEIN-Pad19)") (class "Default")
      (node (ref "IC2") (pin "19") (pinfunction "RLINEIN_19") (pintype "bidirectional"))
    )
    (net (code "61") (name "unconnected-(IC2-XTO-Pad26)") (class "Default")
      (node (ref "IC2") (pin "26") (pinfunction "XTO_26") (pintype "bidirectional"))
    )
    (net (code "62") (name "unconnected-(J2-2_2-Pad3)") (class "Default")
      (node (ref "J2") (pin "3") (pinfunction "2_2_3") (pintype "bidirectional"))
    )
  )
)
